# untitled.net
KiCad netlist of a schematic drawn in EAGLE
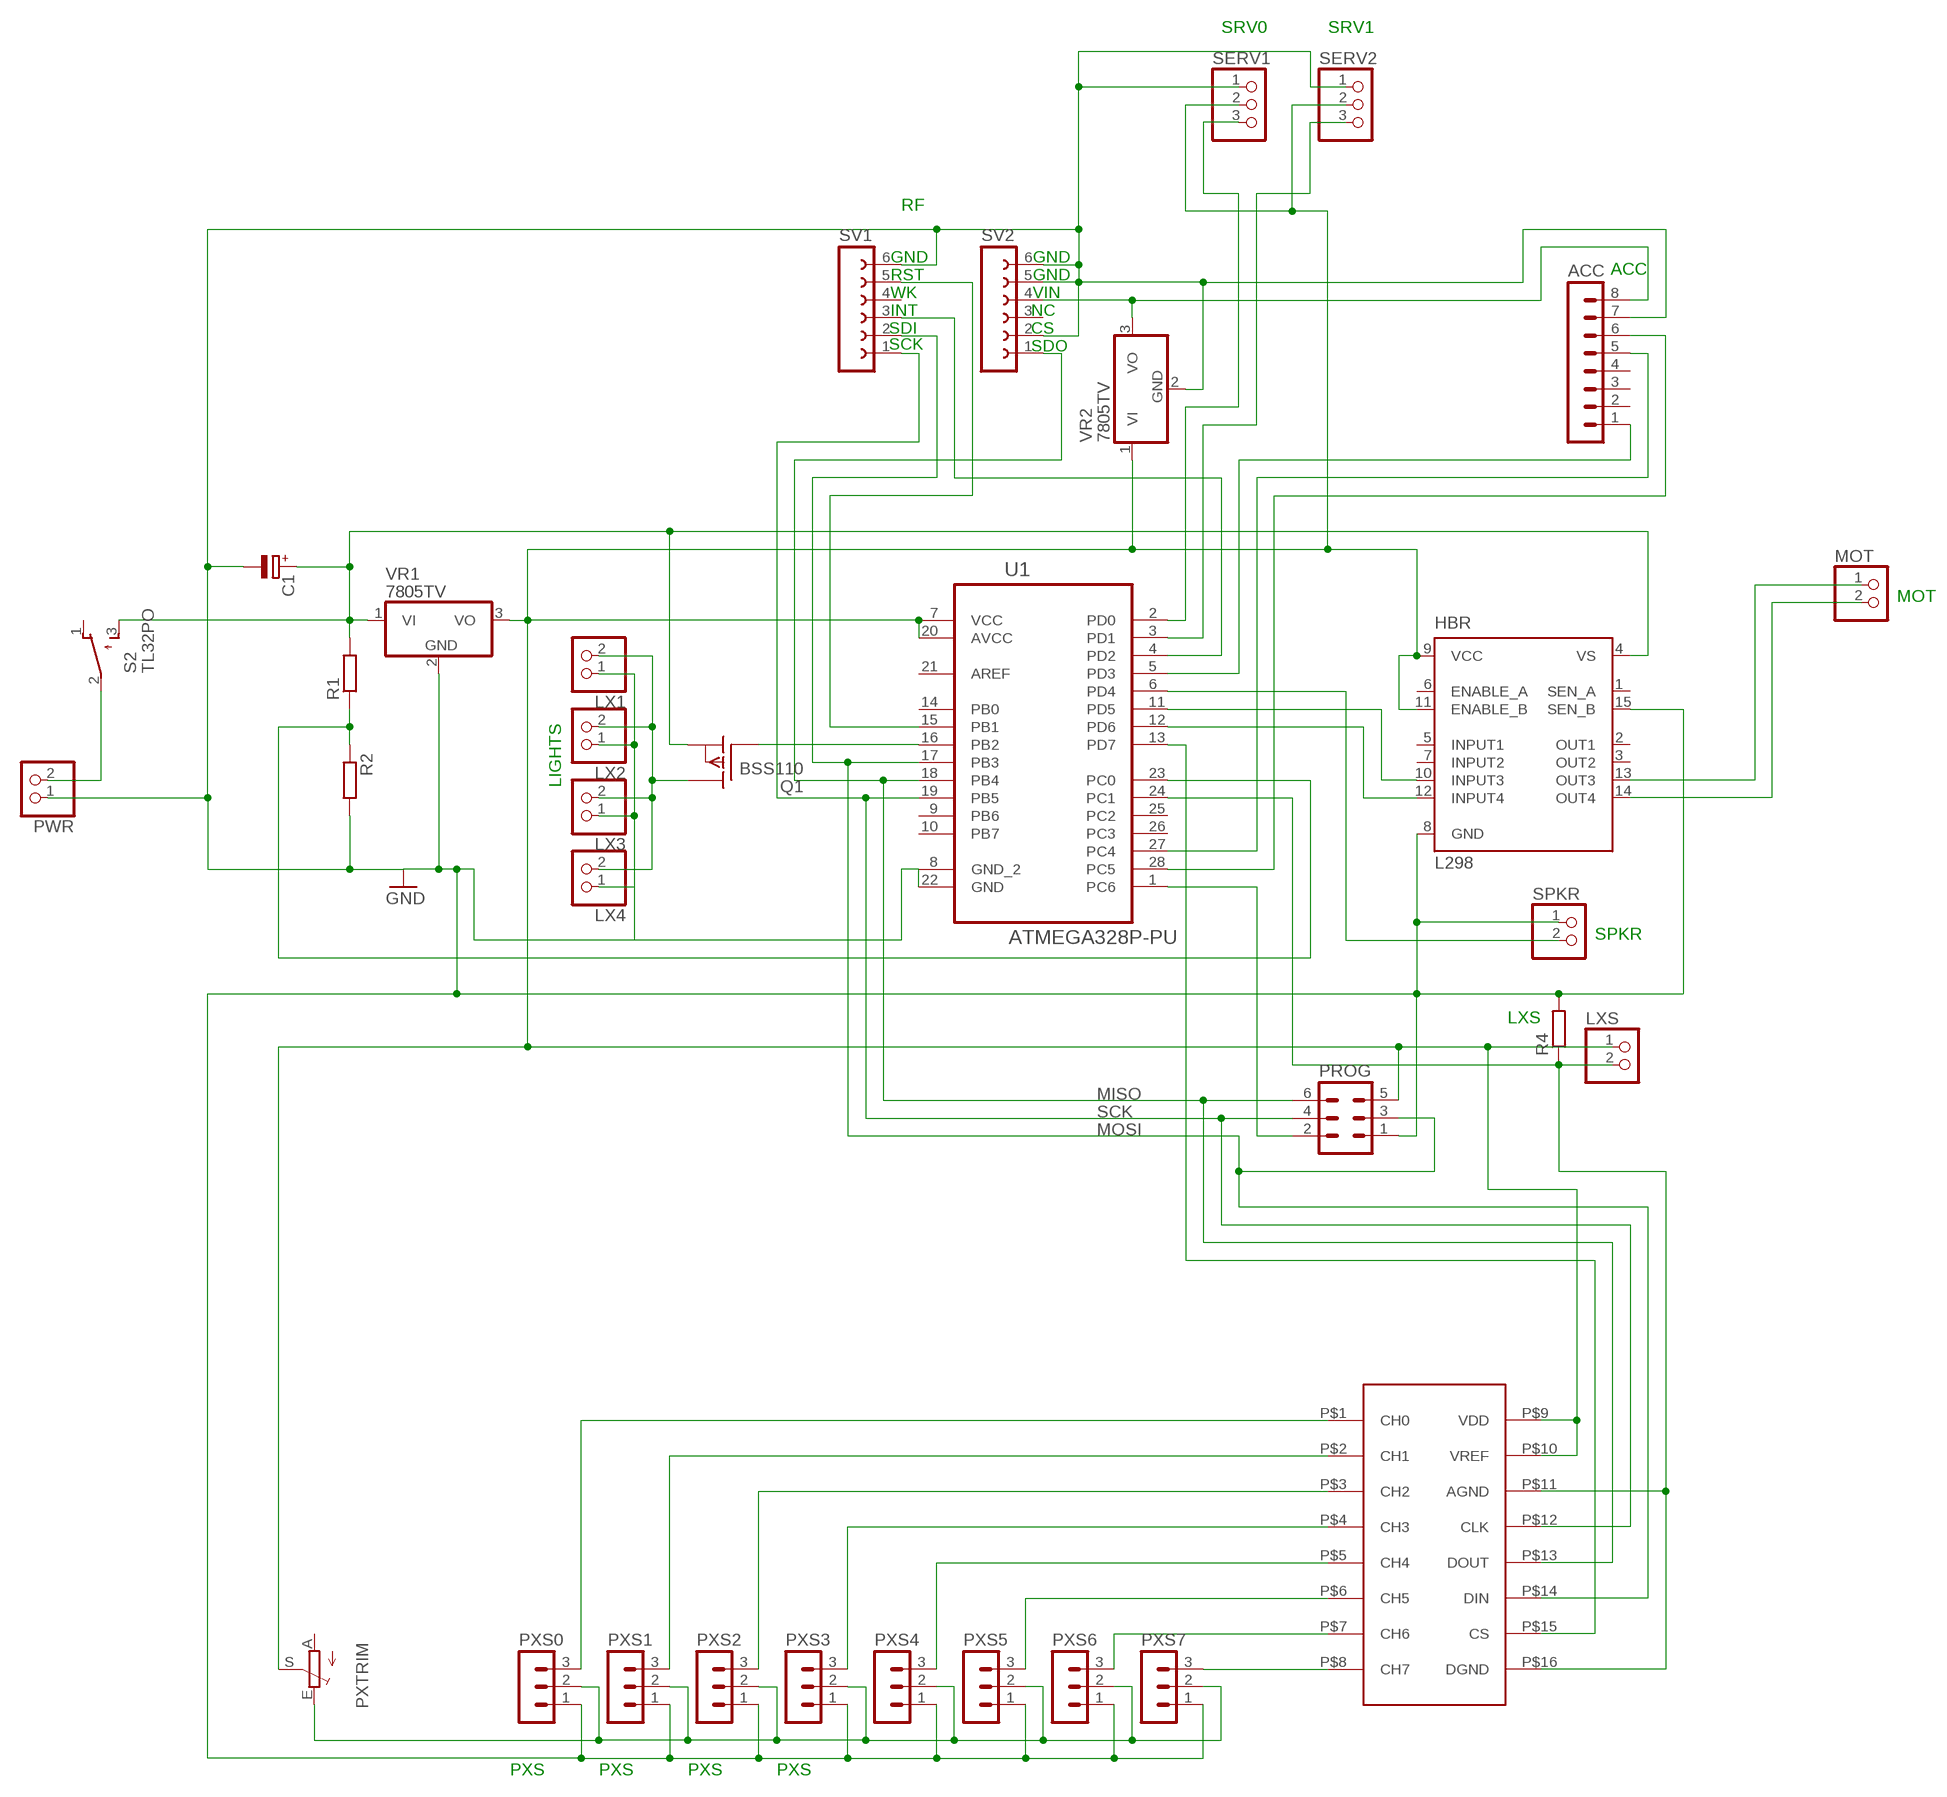
[diagram p0: schematic, sheet 1]

(export (version "E")
  (design (tool "Eeschema 10.0.6"))
  (components
    (comp (ref "ACC")
      (value "MA08-1")
      (footprint "eagle-import:MA08-1")
      (libsource (lib "eagle-import") (part "MA08-1"))
    )
    (comp (ref "C1")
      (value "CPOL-EUE2.5-7")
      (footprint "eagle-import:E2,5-7")
      (libsource (lib "eagle-import") (part "CPOL-EUE2.5-7"))
    )
    (comp (ref "HBR")
      (value "L298")
      (footprint "eagle-import:MULTIWATT-15")
      (fields (field (name "MPN") "L298N"))
      (libsource (lib "eagle-import") (part "L298"))
    )
    (comp (ref "LX1")
      (value "PINHD-1X2")
      (footprint "eagle-import:1X02")
      (libsource (lib "eagle-import") (part "PINHD-1X2"))
    )
    (comp (ref "LX2")
      (value "PINHD-1X2")
      (footprint "eagle-import:1X02")
      (libsource (lib "eagle-import") (part "PINHD-1X2"))
    )
    (comp (ref "LX3")
      (value "PINHD-1X2")
      (footprint "eagle-import:1X02")
      (libsource (lib "eagle-import") (part "PINHD-1X2"))
    )
    (comp (ref "LX4")
      (value "PINHD-1X2")
      (footprint "eagle-import:1X02")
      (libsource (lib "eagle-import") (part "PINHD-1X2"))
    )
    (comp (ref "LXS")
      (value "PINHD-1X2")
      (footprint "eagle-import:1X02")
      (libsource (lib "eagle-import") (part "PINHD-1X2"))
    )
    (comp (ref "MOT")
      (value "PINHD-1X2")
      (footprint "eagle-import:1X02")
      (libsource (lib "eagle-import") (part "PINHD-1X2"))
    )
    (comp (ref "PROG")
      (value "MA03-2")
      (footprint "eagle-import:MA03-2")
      (libsource (lib "eagle-import") (part "MA03-2"))
    )
    (comp (ref "PWR")
      (value "PINHD-1X2")
      (footprint "eagle-import:1X02")
      (libsource (lib "eagle-import") (part "PINHD-1X2"))
    )
    (comp (ref "PXS0")
      (value "MA03-1")
      (footprint "eagle-import:MA03-1")
      (libsource (lib "eagle-import") (part "MA03-1"))
    )
    (comp (ref "PXS1")
      (value "MA03-1")
      (footprint "eagle-import:MA03-1")
      (libsource (lib "eagle-import") (part "MA03-1"))
    )
    (comp (ref "PXS2")
      (value "MA03-1")
      (footprint "eagle-import:MA03-1")
      (libsource (lib "eagle-import") (part "MA03-1"))
    )
    (comp (ref "PXS3")
      (value "MA03-1")
      (footprint "eagle-import:MA03-1")
      (libsource (lib "eagle-import") (part "MA03-1"))
    )
    (comp (ref "PXS4")
      (value "MA03-1")
      (footprint "eagle-import:MA03-1")
      (libsource (lib "eagle-import") (part "MA03-1"))
    )
    (comp (ref "PXS5")
      (value "MA03-1")
      (footprint "eagle-import:MA03-1")
      (libsource (lib "eagle-import") (part "MA03-1"))
    )
    (comp (ref "PXS6")
      (value "MA03-1")
      (footprint "eagle-import:MA03-1")
      (libsource (lib "eagle-import") (part "MA03-1"))
    )
    (comp (ref "PXS7")
      (value "MA03-1")
      (footprint "eagle-import:MA03-1")
      (libsource (lib "eagle-import") (part "MA03-1"))
    )
    (comp (ref "PXTRIM")
      (value "TRIM_EU-CA9V")
      (footprint "eagle-import:CA9V")
      (libsource (lib "eagle-import") (part "TRIM_EU-CA9V"))
    )
    (comp (ref "Q1")
      (value "BSS110")
      (footprint "eagle-import:TO92")
      (libsource (lib "eagle-import") (part "BSS110"))
    )
    (comp (ref "R1")
      (value "R-EU_0309/V")
      (footprint "eagle-import:0309V")
      (libsource (lib "eagle-import") (part "R-EU_0309/V"))
    )
    (comp (ref "R2")
      (value "R-EU_0309/V")
      (footprint "eagle-import:0309V")
      (libsource (lib "eagle-import") (part "R-EU_0309/V"))
    )
    (comp (ref "R4")
      (value "R-EU_0309/V")
      (footprint "eagle-import:0309V")
      (libsource (lib "eagle-import") (part "R-EU_0309/V"))
    )
    (comp (ref "S2")
      (value "TL32PO")
      (footprint "eagle-import:TL3XPO")
      (libsource (lib "eagle-import") (part "TL32PO"))
    )
    (comp (ref "SERV1")
      (value "PINHD-1X3")
      (footprint "eagle-import:1X03")
      (libsource (lib "eagle-import") (part "PINHD-1X3"))
    )
    (comp (ref "SERV2")
      (value "PINHD-1X3")
      (footprint "eagle-import:1X03")
      (libsource (lib "eagle-import") (part "PINHD-1X3"))
    )
    (comp (ref "SPKR")
      (value "PINHD-1X2")
      (footprint "eagle-import:1X02")
      (libsource (lib "eagle-import") (part "PINHD-1X2"))
    )
    (comp (ref "SV1")
      (value "FE06-1")
      (footprint "eagle-import:FE06")
      (libsource (lib "eagle-import") (part "FE06-1"))
    )
    (comp (ref "SV2")
      (value "FE06-1")
      (footprint "eagle-import:FE06")
      (libsource (lib "eagle-import") (part "FE06-1"))
    )
    (comp (ref "U$1")
      (value "MCP3208")
      (footprint "eagle-import:DIP16")
      (libsource (lib "eagle-import") (part "MCP3208"))
    )
    (comp (ref "U1")
      (value "ATMEGA328P-PU")
      (footprint "eagle-import:DIP254P762X457-28")
      (libsource (lib "eagle-import") (part "ATMEGA328P-PU"))
    )
    (comp (ref "VR1")
      (value "7805TV")
      (footprint "eagle-import:TO220V")
      (libsource (lib "eagle-import") (part "78TV05"))
    )
    (comp (ref "VR2")
      (value "7805TV")
      (footprint "eagle-import:TO220V")
      (libsource (lib "eagle-import") (part "78TV05"))
    )
  )
  (nets
    (net (code "1") (name "/MISO") (class "Default")
      (node (ref "PROG") (pin "6") (pinfunction "6_6") (pintype "passive"))
      (node (ref "SV2") (pin "1") (pinfunction "1_1") (pintype "passive"))
      (node (ref "U$1") (pin "P$13") (pinfunction "DOUT_P$13") (pintype "bidirectional"))
      (node (ref "U1") (pin "18") (pinfunction "PB4_18") (pintype "bidirectional"))
    )
    (net (code "2") (name "/MOSI") (class "Default")
      (node (ref "PROG") (pin "3") (pinfunction "3_3") (pintype "passive"))
      (node (ref "SV1") (pin "2") (pinfunction "2_2") (pintype "passive"))
      (node (ref "U$1") (pin "P$14") (pinfunction "DIN_P$14") (pintype "bidirectional"))
      (node (ref "U1") (pin "17") (pinfunction "PB3_17") (pintype "bidirectional"))
    )
    (net (code "3") (name "/SCK") (class "Default")
      (node (ref "PROG") (pin "4") (pinfunction "4_4") (pintype "passive"))
      (node (ref "SV1") (pin "1") (pinfunction "1_1") (pintype "passive"))
      (node (ref "U$1") (pin "P$12") (pinfunction "CLK_P$12") (pintype "bidirectional"))
      (node (ref "U1") (pin "19") (pinfunction "PB5_19") (pintype "bidirectional"))
    )
    (net (code "4") (name "GND") (class "Default")
      (node (ref "ACC") (pin "7") (pinfunction "7_7") (pintype "passive"))
      (node (ref "C1") (pin "-") (pinfunction "-_-") (pintype "passive"))
      (node (ref "HBR") (pin "15") (pinfunction "SEN_B_15") (pintype "input"))
      (node (ref "HBR") (pin "8") (pinfunction "GND_8") (pintype "power_in"))
      (node (ref "LX1") (pin "1") (pinfunction "1_1") (pintype "passive"))
      (node (ref "LX2") (pin "1") (pinfunction "1_1") (pintype "passive"))
      (node (ref "LX3") (pin "1") (pinfunction "1_1") (pintype "passive"))
      (node (ref "LX4") (pin "1") (pinfunction "1_1") (pintype "passive"))
      (node (ref "PROG") (pin "1") (pinfunction "1_1") (pintype "passive"))
      (node (ref "PWR") (pin "1") (pinfunction "1_1") (pintype "passive"))
      (node (ref "PXS0") (pin "1") (pinfunction "1_1") (pintype "passive"))
      (node (ref "PXS1") (pin "1") (pinfunction "1_1") (pintype "passive"))
      (node (ref "PXS2") (pin "1") (pinfunction "1_1") (pintype "passive"))
      (node (ref "PXS3") (pin "1") (pinfunction "1_1") (pintype "passive"))
      (node (ref "PXS4") (pin "1") (pinfunction "1_1") (pintype "passive"))
      (node (ref "PXS5") (pin "1") (pinfunction "1_1") (pintype "passive"))
      (node (ref "PXS6") (pin "1") (pinfunction "1_1") (pintype "passive"))
      (node (ref "PXS7") (pin "1") (pinfunction "1_1") (pintype "passive"))
      (node (ref "R2") (pin "2") (pinfunction "2_2") (pintype "passive"))
      (node (ref "R4") (pin "2") (pinfunction "2_2") (pintype "passive"))
      (node (ref "SERV1") (pin "1") (pinfunction "1_1") (pintype "passive"))
      (node (ref "SERV2") (pin "1") (pinfunction "1_1") (pintype "passive"))
      (node (ref "SPKR") (pin "1") (pinfunction "1_1") (pintype "passive"))
      (node (ref "SV1") (pin "6") (pinfunction "6_6") (pintype "passive"))
      (node (ref "SV2") (pin "2") (pinfunction "2_2") (pintype "passive"))
      (node (ref "SV2") (pin "5") (pinfunction "5_5") (pintype "passive"))
      (node (ref "SV2") (pin "6") (pinfunction "6_6") (pintype "passive"))
      (node (ref "U1") (pin "22") (pinfunction "GND_22") (pintype "passive"))
      (node (ref "U1") (pin "8") (pinfunction "GND_2_8") (pintype "passive"))
      (node (ref "VR1") (pin "2") (pinfunction "GND_2") (pintype "passive"))
      (node (ref "VR2") (pin "2") (pinfunction "GND_2") (pintype "passive"))
    )
    (net (code "5") (name "Net-(HBR-ENABLE_B)") (class "Default")
      (node (ref "HBR") (pin "11") (pinfunction "ENABLE_B_11") (pintype "input"))
      (node (ref "HBR") (pin "9") (pinfunction "VCC_9") (pintype "power_in"))
      (node (ref "LXS") (pin "1") (pinfunction "1_1") (pintype "passive"))
      (node (ref "PROG") (pin "5") (pinfunction "5_5") (pintype "passive"))
      (node (ref "PXTRIM") (pin "S") (pinfunction "S_S") (pintype "passive"))
      (node (ref "SERV1") (pin "2") (pinfunction "2_2") (pintype "passive"))
      (node (ref "SERV2") (pin "2") (pinfunction "2_2") (pintype "passive"))
      (node (ref "U$1") (pin "P$10") (pinfunction "VREF_P$10") (pintype "bidirectional"))
      (node (ref "U$1") (pin "P$9") (pinfunction "VDD_P$9") (pintype "bidirectional"))
      (node (ref "U1") (pin "20") (pinfunction "AVCC_20") (pintype "power_in"))
      (node (ref "U1") (pin "7") (pinfunction "VCC_7") (pintype "power_in"))
      (node (ref "VR1") (pin "3") (pinfunction "VO_3") (pintype "passive"))
      (node (ref "VR2") (pin "1") (pinfunction "VI_1") (pintype "input"))
    )
    (net (code "6") (name "Net-(HBR-INPUT3)") (class "Default")
      (node (ref "HBR") (pin "10") (pinfunction "INPUT3_10") (pintype "input"))
      (node (ref "U1") (pin "11") (pinfunction "PD5_11") (pintype "bidirectional"))
    )
    (net (code "7") (name "Net-(HBR-INPUT4)") (class "Default")
      (node (ref "HBR") (pin "12") (pinfunction "INPUT4_12") (pintype "input"))
      (node (ref "U1") (pin "12") (pinfunction "PD6_12") (pintype "bidirectional"))
    )
    (net (code "8") (name "Net-(HBR-OUT3)") (class "Default")
      (node (ref "HBR") (pin "13") (pinfunction "OUT3_13") (pintype "output"))
      (node (ref "MOT") (pin "1") (pinfunction "1_1") (pintype "passive"))
    )
    (net (code "9") (name "Net-(HBR-OUT4)") (class "Default")
      (node (ref "HBR") (pin "14") (pinfunction "OUT4_14") (pintype "output"))
      (node (ref "MOT") (pin "2") (pinfunction "2_2") (pintype "passive"))
    )
    (net (code "10") (name "Net-(HBR-VS)") (class "Default")
      (node (ref "C1") (pin "+") (pinfunction "+_+") (pintype "passive"))
      (node (ref "HBR") (pin "4") (pinfunction "VS_4") (pintype "power_in"))
      (node (ref "Q1") (pin "1") (pinfunction "S_1") (pintype "passive"))
      (node (ref "R1") (pin "2") (pinfunction "2_2") (pintype "passive"))
      (node (ref "S2") (pin "3") (pinfunction "S_3") (pintype "passive"))
      (node (ref "VR1") (pin "1") (pinfunction "VI_1") (pintype "input"))
    )
    (net (code "11") (name "Net-(PXS0-Pad2)") (class "Default")
      (node (ref "PXS0") (pin "2") (pinfunction "2_2") (pintype "passive"))
      (node (ref "PXS1") (pin "2") (pinfunction "2_2") (pintype "passive"))
      (node (ref "PXS2") (pin "2") (pinfunction "2_2") (pintype "passive"))
      (node (ref "PXS3") (pin "2") (pinfunction "2_2") (pintype "passive"))
      (node (ref "PXS4") (pin "2") (pinfunction "2_2") (pintype "passive"))
      (node (ref "PXS5") (pin "2") (pinfunction "2_2") (pintype "passive"))
      (node (ref "PXS6") (pin "2") (pinfunction "2_2") (pintype "passive"))
      (node (ref "PXS7") (pin "2") (pinfunction "2_2") (pintype "passive"))
      (node (ref "PXTRIM") (pin "E") (pinfunction "E_E") (pintype "passive"))
    )
    (net (code "12") (name "Net-(Q1-D)") (class "Default")
      (node (ref "LX1") (pin "2") (pinfunction "2_2") (pintype "passive"))
      (node (ref "LX2") (pin "2") (pinfunction "2_2") (pintype "passive"))
      (node (ref "LX3") (pin "2") (pinfunction "2_2") (pintype "passive"))
      (node (ref "LX4") (pin "2") (pinfunction "2_2") (pintype "passive"))
      (node (ref "Q1") (pin "3") (pinfunction "D_3") (pintype "passive"))
    )
    (net (code "13") (name "Net-(Q1-G)") (class "Default")
      (node (ref "Q1") (pin "2") (pinfunction "G_2") (pintype "passive"))
      (node (ref "U1") (pin "16") (pinfunction "PB2_16") (pintype "bidirectional"))
    )
    (net (code "14") (name "Net-(S2-P)") (class "Default")
      (node (ref "PWR") (pin "2") (pinfunction "2_2") (pintype "passive"))
      (node (ref "S2") (pin "2") (pinfunction "P_2") (pintype "passive"))
    )
    (net (code "15") (name "Net-(U$1-AGND)") (class "Default")
      (node (ref "LXS") (pin "2") (pinfunction "2_2") (pintype "passive"))
      (node (ref "R4") (pin "1") (pinfunction "1_1") (pintype "passive"))
      (node (ref "U$1") (pin "P$11") (pinfunction "AGND_P$11") (pintype "bidirectional"))
      (node (ref "U$1") (pin "P$16") (pinfunction "DGND_P$16") (pintype "bidirectional"))
      (node (ref "U1") (pin "24") (pinfunction "PC1_24") (pintype "bidirectional"))
    )
    (net (code "16") (name "Net-(U$1-CH0)") (class "Default")
      (node (ref "PXS0") (pin "3") (pinfunction "3_3") (pintype "passive"))
      (node (ref "U$1") (pin "P$1") (pinfunction "CH0_P$1") (pintype "bidirectional"))
    )
    (net (code "17") (name "Net-(U$1-CH1)") (class "Default")
      (node (ref "PXS1") (pin "3") (pinfunction "3_3") (pintype "passive"))
      (node (ref "U$1") (pin "P$2") (pinfunction "CH1_P$2") (pintype "bidirectional"))
    )
    (net (code "18") (name "Net-(U$1-CH2)") (class "Default")
      (node (ref "PXS2") (pin "3") (pinfunction "3_3") (pintype "passive"))
      (node (ref "U$1") (pin "P$3") (pinfunction "CH2_P$3") (pintype "bidirectional"))
    )
    (net (code "19") (name "Net-(U$1-CH3)") (class "Default")
      (node (ref "PXS3") (pin "3") (pinfunction "3_3") (pintype "passive"))
      (node (ref "U$1") (pin "P$4") (pinfunction "CH3_P$4") (pintype "bidirectional"))
    )
    (net (code "20") (name "Net-(U$1-CH4)") (class "Default")
      (node (ref "PXS4") (pin "3") (pinfunction "3_3") (pintype "passive"))
      (node (ref "U$1") (pin "P$5") (pinfunction "CH4_P$5") (pintype "bidirectional"))
    )
    (net (code "21") (name "Net-(U$1-CH5)") (class "Default")
      (node (ref "PXS5") (pin "3") (pinfunction "3_3") (pintype "passive"))
      (node (ref "U$1") (pin "P$6") (pinfunction "CH5_P$6") (pintype "bidirectional"))
    )
    (net (code "22") (name "Net-(U$1-CH6)") (class "Default")
      (node (ref "PXS6") (pin "3") (pinfunction "3_3") (pintype "passive"))
      (node (ref "U$1") (pin "P$7") (pinfunction "CH6_P$7") (pintype "bidirectional"))
    )
    (net (code "23") (name "Net-(U$1-CH7)") (class "Default")
      (node (ref "PXS7") (pin "3") (pinfunction "3_3") (pintype "passive"))
      (node (ref "U$1") (pin "P$8") (pinfunction "CH7_P$8") (pintype "bidirectional"))
    )
    (net (code "24") (name "Net-(U$1-CS)") (class "Default")
      (node (ref "U$1") (pin "P$15") (pinfunction "CS_P$15") (pintype "bidirectional"))
      (node (ref "U1") (pin "13") (pinfunction "PD7_13") (pintype "bidirectional"))
    )
    (net (code "25") (name "Net-(U1-PB1)") (class "Default")
      (node (ref "SV1") (pin "5") (pinfunction "5_5") (pintype "passive"))
      (node (ref "U1") (pin "15") (pinfunction "PB1_15") (pintype "bidirectional"))
    )
    (net (code "26") (name "Net-(U1-PC0)") (class "Default")
      (node (ref "R1") (pin "1") (pinfunction "1_1") (pintype "passive"))
      (node (ref "R2") (pin "1") (pinfunction "1_1") (pintype "passive"))
      (node (ref "U1") (pin "23") (pinfunction "PC0_23") (pintype "bidirectional"))
    )
    (net (code "27") (name "Net-(U1-PC4)") (class "Default")
      (node (ref "ACC") (pin "5") (pinfunction "5_5") (pintype "passive"))
      (node (ref "U1") (pin "27") (pinfunction "PC4_27") (pintype "bidirectional"))
    )
    (net (code "28") (name "Net-(U1-PC5)") (class "Default")
      (node (ref "ACC") (pin "6") (pinfunction "6_6") (pintype "passive"))
      (node (ref "U1") (pin "28") (pinfunction "PC5_28") (pintype "bidirectional"))
    )
    (net (code "29") (name "Net-(U1-PC6)") (class "Default")
      (node (ref "PROG") (pin "2") (pinfunction "2_2") (pintype "passive"))
      (node (ref "U1") (pin "1") (pinfunction "PC6_1") (pintype "bidirectional"))
    )
    (net (code "30") (name "Net-(U1-PD0)") (class "Default")
      (node (ref "SERV1") (pin "3") (pinfunction "3_3") (pintype "passive"))
      (node (ref "U1") (pin "2") (pinfunction "PD0_2") (pintype "bidirectional"))
    )
    (net (code "31") (name "Net-(U1-PD1)") (class "Default")
      (node (ref "SERV2") (pin "3") (pinfunction "3_3") (pintype "passive"))
      (node (ref "U1") (pin "3") (pinfunction "PD1_3") (pintype "bidirectional"))
    )
    (net (code "32") (name "Net-(U1-PD2)") (class "Default")
      (node (ref "SV1") (pin "3") (pinfunction "3_3") (pintype "passive"))
      (node (ref "U1") (pin "4") (pinfunction "PD2_4") (pintype "bidirectional"))
    )
    (net (code "33") (name "Net-(U1-PD3)") (class "Default")
      (node (ref "ACC") (pin "1") (pinfunction "1_1") (pintype "passive"))
      (node (ref "U1") (pin "5") (pinfunction "PD3_5") (pintype "bidirectional"))
    )
    (net (code "34") (name "Net-(U1-PD4)") (class "Default")
      (node (ref "SPKR") (pin "2") (pinfunction "2_2") (pintype "passive"))
      (node (ref "U1") (pin "6") (pinfunction "PD4_6") (pintype "bidirectional"))
    )
    (net (code "35") (name "Net-(VR2-VO)") (class "Default")
      (node (ref "ACC") (pin "8") (pinfunction "8_8") (pintype "passive"))
      (node (ref "SV2") (pin "4") (pinfunction "4_4") (pintype "passive"))
      (node (ref "VR2") (pin "3") (pinfunction "VO_3") (pintype "passive"))
    )
    (net (code "36") (name "unconnected-(ACC-Pad2)") (class "Default")
      (node (ref "ACC") (pin "2") (pinfunction "2_2") (pintype "passive"))
    )
    (net (code "37") (name "unconnected-(ACC-Pad3)") (class "Default")
      (node (ref "ACC") (pin "3") (pinfunction "3_3") (pintype "passive"))
    )
    (net (code "38") (name "unconnected-(ACC-Pad4)") (class "Default")
      (node (ref "ACC") (pin "4") (pinfunction "4_4") (pintype "passive"))
    )
    (net (code "39") (name "unconnected-(HBR-ENABLE_A-Pad6)") (class "Default")
      (node (ref "HBR") (pin "6") (pinfunction "ENABLE_A_6") (pintype "input"))
    )
    (net (code "40") (name "unconnected-(HBR-INPUT1-Pad5)") (class "Default")
      (node (ref "HBR") (pin "5") (pinfunction "INPUT1_5") (pintype "input"))
    )
    (net (code "41") (name "unconnected-(HBR-INPUT2-Pad7)") (class "Default")
      (node (ref "HBR") (pin "7") (pinfunction "INPUT2_7") (pintype "input"))
    )
    (net (code "42") (name "unconnected-(HBR-OUT1-Pad2)") (class "Default")
      (node (ref "HBR") (pin "2") (pinfunction "OUT1_2") (pintype "output"))
    )
    (net (code "43") (name "unconnected-(HBR-OUT2-Pad3)") (class "Default")
      (node (ref "HBR") (pin "3") (pinfunction "OUT2_3") (pintype "output"))
    )
    (net (code "44") (name "unconnected-(HBR-SEN_A-Pad1)") (class "Default")
      (node (ref "HBR") (pin "1") (pinfunction "SEN_A_1") (pintype "input"))
    )
    (net (code "45") (name "unconnected-(PXTRIM-PadA)") (class "Default")
      (node (ref "PXTRIM") (pin "A") (pinfunction "A_A") (pintype "passive"))
    )
    (net (code "46") (name "unconnected-(S2-O-Pad1)") (class "Default")
      (node (ref "S2") (pin "1") (pinfunction "O_1") (pintype "passive"))
    )
    (net (code "47") (name "unconnected-(SV1-Pad4)") (class "Default")
      (node (ref "SV1") (pin "4") (pinfunction "4_4") (pintype "passive"))
    )
    (net (code "48") (name "unconnected-(SV2-Pad3)") (class "Default")
      (node (ref "SV2") (pin "3") (pinfunction "3_3") (pintype "passive"))
    )
    (net (code "49") (name "unconnected-(U1-AREF-Pad21)") (class "Default")
      (node (ref "U1") (pin "21") (pinfunction "AREF_21") (pintype "input"))
    )
    (net (code "50") (name "unconnected-(U1-PB0-Pad14)") (class "Default")
      (node (ref "U1") (pin "14") (pinfunction "PB0_14") (pintype "bidirectional"))
    )
    (net (code "51") (name "unconnected-(U1-PB6-Pad9)") (class "Default")
      (node (ref "U1") (pin "9") (pinfunction "PB6_9") (pintype "bidirectional"))
    )
    (net (code "52") (name "unconnected-(U1-PB7-Pad10)") (class "Default")
      (node (ref "U1") (pin "10") (pinfunction "PB7_10") (pintype "bidirectional"))
    )
    (net (code "53") (name "unconnected-(U1-PC2-Pad25)") (class "Default")
      (node (ref "U1") (pin "25") (pinfunction "PC2_25") (pintype "bidirectional"))
    )
    (net (code "54") (name "unconnected-(U1-PC3-Pad26)") (class "Default")
      (node (ref "U1") (pin "26") (pinfunction "PC3_26") (pintype "bidirectional"))
    )
  )
)
